# I2C_TH_Sensor_Socket.net
KiCad netlist of a schematic drawn in Altium Designer
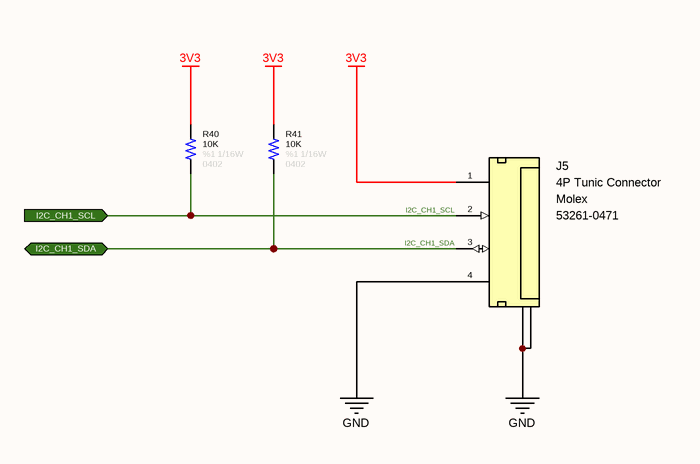
[diagram p0: I2C TH Sensor Socket.SchDoc]

(export (version "E")
  (design (tool "Eeschema 10.0.6"))
  (components
    (comp (ref "J5")
      (value "4P SMD Tunic Connector")
      (footprint "Connector_Tunic 4P")
      (description "Mini Tunic Connector with 4P")
      (fields
        (field (name "MANUFACTURER NAME") "Molex")
        (field (name "MANUFACTURER PART NUMBER") "53261-0471")
      )
      (libsource (lib "Akkoyun") (part "Connector - Mini Tunic 4P (1.25)"))
    )
    (comp (ref "R40")
      (value "10K")
      (footprint "RESISTOR_0402")
      (description "Thick Film Resistors - SMD 1/16 W 10 KOhm 1%")
      (fields
        (field (name "MANUFACTURER PART NUMBER") "CRCW040210K0FKED")
        (field (name "TOLERANCE") "%1")
        (field (name "CASE") "0402")
        (field (name "POWER") "1/16W")
        (field (name "Comment") "10K - 0402 - %1 - 1/16W")
      )
      (libsource (lib "Akkoyun") (part "Resistor - 10K [0402]"))
    )
    (comp (ref "R41")
      (value "10K")
      (footprint "RESISTOR_0402")
      (description "Thick Film Resistors - SMD 1/16 W 10 KOhm 1%")
      (fields
        (field (name "MANUFACTURER PART NUMBER") "CRCW040210K0FKED")
        (field (name "TOLERANCE") "%1")
        (field (name "CASE") "0402")
        (field (name "POWER") "1/16W")
        (field (name "Comment") "10K - 0402 - %1 - 1/16W")
      )
      (libsource (lib "Akkoyun") (part "Resistor - 10K [0402]"))
    )
  )
  (nets
    (net (code "1") (name "/I2C_CH1_SCL") (class "Default")
      (node (ref "J5") (pin "2") (pinfunction "Pin-2_2") (pintype "input"))
      (node (ref "R40") (pin "1") (pinfunction "1_1") (pintype "passive"))
    )
    (net (code "2") (name "/I2C_CH1_SDA") (class "Default")
      (node (ref "J5") (pin "3") (pinfunction "Pin-3_3") (pintype "bidirectional"))
      (node (ref "R41") (pin "1") (pinfunction "1_1") (pintype "passive"))
    )
    (net (code "3") (name "3V3") (class "Default")
      (node (ref "J5") (pin "1") (pinfunction "Pin-1_1") (pintype "passive"))
      (node (ref "R40") (pin "2") (pinfunction "2_2") (pintype "passive"))
      (node (ref "R41") (pin "2") (pinfunction "2_2") (pintype "passive"))
    )
    (net (code "4") (name "GND") (class "Default")
      (node (ref "J5") (pin "4") (pinfunction "Pin-4_4") (pintype "passive"))
      (node (ref "J5") (pin "5") (pinfunction "GND_5") (pintype "passive"))
      (node (ref "J5") (pin "6") (pinfunction "GND_6") (pintype "passive"))
    )
  )
)
